# Bombas.net
KiCad netlist of a schematic drawn in Altium Designer
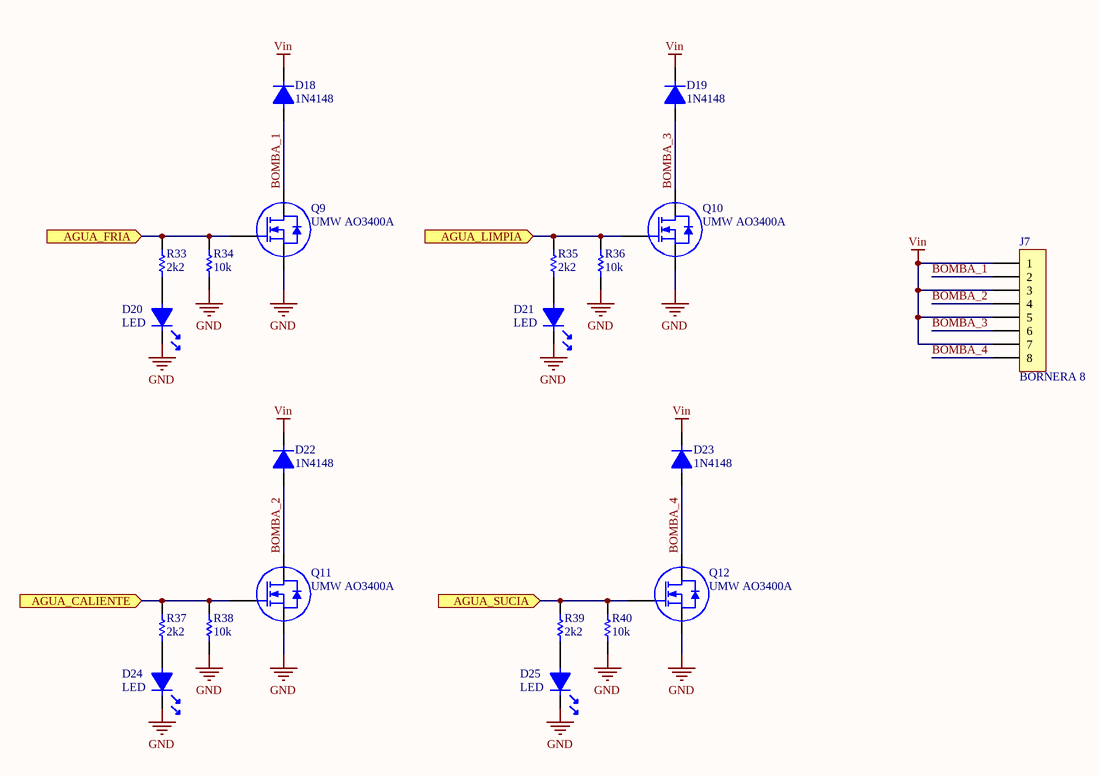
[diagram p0: Bombas.SchDoc]

(export (version "E")
  (design (tool "Eeschema 10.0.6"))
  (components
    (comp (ref "D18") (value "1N4148") (footprint "1206K") (libsource (lib "LIBPIOIX") (part "DIODO")))
    (comp (ref "D19") (value "1N4148") (footprint "1206K") (libsource (lib "LIBPIOIX") (part "DIODO")))
    (comp (ref "D20") (value "LED") (footprint "LED0805") (libsource (lib "LIBPIOIX") (part "LED")))
    (comp (ref "D21") (value "LED") (footprint "LED0805") (libsource (lib "LIBPIOIX") (part "LED")))
    (comp (ref "D22") (value "1N4148") (footprint "1206K") (libsource (lib "LIBPIOIX") (part "DIODO")))
    (comp (ref "D23") (value "1N4148") (footprint "1206K") (libsource (lib "LIBPIOIX") (part "DIODO")))
    (comp (ref "D24") (value "LED") (footprint "LED0805") (libsource (lib "LIBPIOIX") (part "LED")))
    (comp (ref "D25") (value "LED") (footprint "LED0805") (libsource (lib "LIBPIOIX") (part "LED")))
    (comp (ref "J7")
      (value "BORNERA 8")
      (footprint "BORNERA8")
      (libsource (lib "LIBPIOIX") (part "BORNERA 8"))
    )
    (comp (ref "Q9") (value "UMW AO3400A") (footprint "SOT23") (libsource (lib "LIBPIOIX") (part "MOSFET N")))
    (comp (ref "Q10")
      (value "UMW AO3400A")
      (footprint "SOT23")
      (libsource (lib "LIBPIOIX") (part "MOSFET N"))
    )
    (comp (ref "Q11")
      (value "UMW AO3400A")
      (footprint "SOT23")
      (libsource (lib "LIBPIOIX") (part "MOSFET N"))
    )
    (comp (ref "Q12")
      (value "UMW AO3400A")
      (footprint "SOT23")
      (libsource (lib "LIBPIOIX") (part "MOSFET N"))
    )
    (comp (ref "R33") (value "2k2") (footprint "0805") (libsource (lib "LIBPIOIX") (part "RES")))
    (comp (ref "R34") (value "10k") (footprint "0805") (libsource (lib "LIBPIOIX") (part "RES")))
    (comp (ref "R35") (value "2k2") (footprint "0805") (libsource (lib "LIBPIOIX") (part "RES")))
    (comp (ref "R36") (value "10k") (footprint "0805") (libsource (lib "LIBPIOIX") (part "RES")))
    (comp (ref "R37") (value "2k2") (footprint "0805") (libsource (lib "LIBPIOIX") (part "RES")))
    (comp (ref "R38") (value "10k") (footprint "0805") (libsource (lib "LIBPIOIX") (part "RES")))
    (comp (ref "R39") (value "2k2") (footprint "0805") (libsource (lib "LIBPIOIX") (part "RES")))
    (comp (ref "R40") (value "10k") (footprint "0805") (libsource (lib "LIBPIOIX") (part "RES")))
  )
  (nets
    (net (code "1") (name "/AGUA_CALIENTE") (class "Default")
      (node (ref "Q11") (pin "1") (pinfunction "G_1") (pintype "passive"))
      (node (ref "R37") (pin "2") (pinfunction "2_2") (pintype "passive"))
      (node (ref "R38") (pin "2") (pinfunction "2_2") (pintype "passive"))
    )
    (net (code "2") (name "/AGUA_FRIA") (class "Default")
      (node (ref "Q9") (pin "1") (pinfunction "G_1") (pintype "passive"))
      (node (ref "R33") (pin "2") (pinfunction "2_2") (pintype "passive"))
      (node (ref "R34") (pin "2") (pinfunction "2_2") (pintype "passive"))
    )
    (net (code "3") (name "/AGUA_LIMPIA") (class "Default")
      (node (ref "Q10") (pin "1") (pinfunction "G_1") (pintype "passive"))
      (node (ref "R35") (pin "2") (pinfunction "2_2") (pintype "passive"))
      (node (ref "R36") (pin "2") (pinfunction "2_2") (pintype "passive"))
    )
    (net (code "4") (name "/AGUA_SUCIA") (class "Default")
      (node (ref "Q12") (pin "1") (pinfunction "G_1") (pintype "passive"))
      (node (ref "R39") (pin "2") (pinfunction "2_2") (pintype "passive"))
      (node (ref "R40") (pin "2") (pinfunction "2_2") (pintype "passive"))
    )
    (net (code "5") (name "/BOMBA_1") (class "Default")
      (node (ref "D18") (pin "1") (pinfunction "1_1") (pintype "passive"))
      (node (ref "J7") (pin "2") (pinfunction "2_2") (pintype "passive"))
      (node (ref "Q9") (pin "2") (pinfunction "D_2") (pintype "passive"))
    )
    (net (code "6") (name "/BOMBA_2") (class "Default")
      (node (ref "D22") (pin "1") (pinfunction "1_1") (pintype "passive"))
      (node (ref "J7") (pin "4") (pinfunction "4_4") (pintype "passive"))
      (node (ref "Q11") (pin "2") (pinfunction "D_2") (pintype "passive"))
    )
    (net (code "7") (name "/BOMBA_3") (class "Default")
      (node (ref "D19") (pin "1") (pinfunction "1_1") (pintype "passive"))
      (node (ref "J7") (pin "6") (pinfunction "6_6") (pintype "passive"))
      (node (ref "Q10") (pin "2") (pinfunction "D_2") (pintype "passive"))
    )
    (net (code "8") (name "/BOMBA_4") (class "Default")
      (node (ref "D23") (pin "1") (pinfunction "1_1") (pintype "passive"))
      (node (ref "J7") (pin "8") (pinfunction "8_8") (pintype "passive"))
      (node (ref "Q12") (pin "2") (pinfunction "D_2") (pintype "passive"))
    )
    (net (code "9") (name "GND") (class "Default")
      (node (ref "D20") (pin "2") (pinfunction "2_2") (pintype "passive"))
      (node (ref "D21") (pin "2") (pinfunction "2_2") (pintype "passive"))
      (node (ref "D24") (pin "2") (pinfunction "2_2") (pintype "passive"))
      (node (ref "D25") (pin "2") (pinfunction "2_2") (pintype "passive"))
      (node (ref "Q10") (pin "3") (pinfunction "S_3") (pintype "passive"))
      (node (ref "Q11") (pin "3") (pinfunction "S_3") (pintype "passive"))
      (node (ref "Q12") (pin "3") (pinfunction "S_3") (pintype "passive"))
      (node (ref "Q9") (pin "3") (pinfunction "S_3") (pintype "passive"))
      (node (ref "R34") (pin "1") (pinfunction "1_1") (pintype "passive"))
      (node (ref "R36") (pin "1") (pinfunction "1_1") (pintype "passive"))
      (node (ref "R38") (pin "1") (pinfunction "1_1") (pintype "passive"))
      (node (ref "R40") (pin "1") (pinfunction "1_1") (pintype "passive"))
    )
    (net (code "10") (name "Net-(D20-Pad1)") (class "Default")
      (node (ref "D20") (pin "1") (pinfunction "1_1") (pintype "passive"))
      (node (ref "R33") (pin "1") (pinfunction "1_1") (pintype "passive"))
    )
    (net (code "11") (name "Net-(D21-Pad1)") (class "Default")
      (node (ref "D21") (pin "1") (pinfunction "1_1") (pintype "passive"))
      (node (ref "R35") (pin "1") (pinfunction "1_1") (pintype "passive"))
    )
    (net (code "12") (name "Net-(D24-Pad1)") (class "Default")
      (node (ref "D24") (pin "1") (pinfunction "1_1") (pintype "passive"))
      (node (ref "R37") (pin "1") (pinfunction "1_1") (pintype "passive"))
    )
    (net (code "13") (name "Net-(D25-Pad1)") (class "Default")
      (node (ref "D25") (pin "1") (pinfunction "1_1") (pintype "passive"))
      (node (ref "R39") (pin "1") (pinfunction "1_1") (pintype "passive"))
    )
    (net (code "14") (name "Vin") (class "Default")
      (node (ref "D18") (pin "2") (pinfunction "2_2") (pintype "passive"))
      (node (ref "D19") (pin "2") (pinfunction "2_2") (pintype "passive"))
      (node (ref "D22") (pin "2") (pinfunction "2_2") (pintype "passive"))
      (node (ref "D23") (pin "2") (pinfunction "2_2") (pintype "passive"))
      (node (ref "J7") (pin "1") (pinfunction "1_1") (pintype "passive"))
      (node (ref "J7") (pin "3") (pinfunction "3_3") (pintype "passive"))
      (node (ref "J7") (pin "5") (pinfunction "5_5") (pintype "passive"))
      (node (ref "J7") (pin "7") (pinfunction "7_7") (pintype "passive"))
    )
  )
)
